# Power_Management.net
KiCad netlist of a schematic drawn in Altium Designer
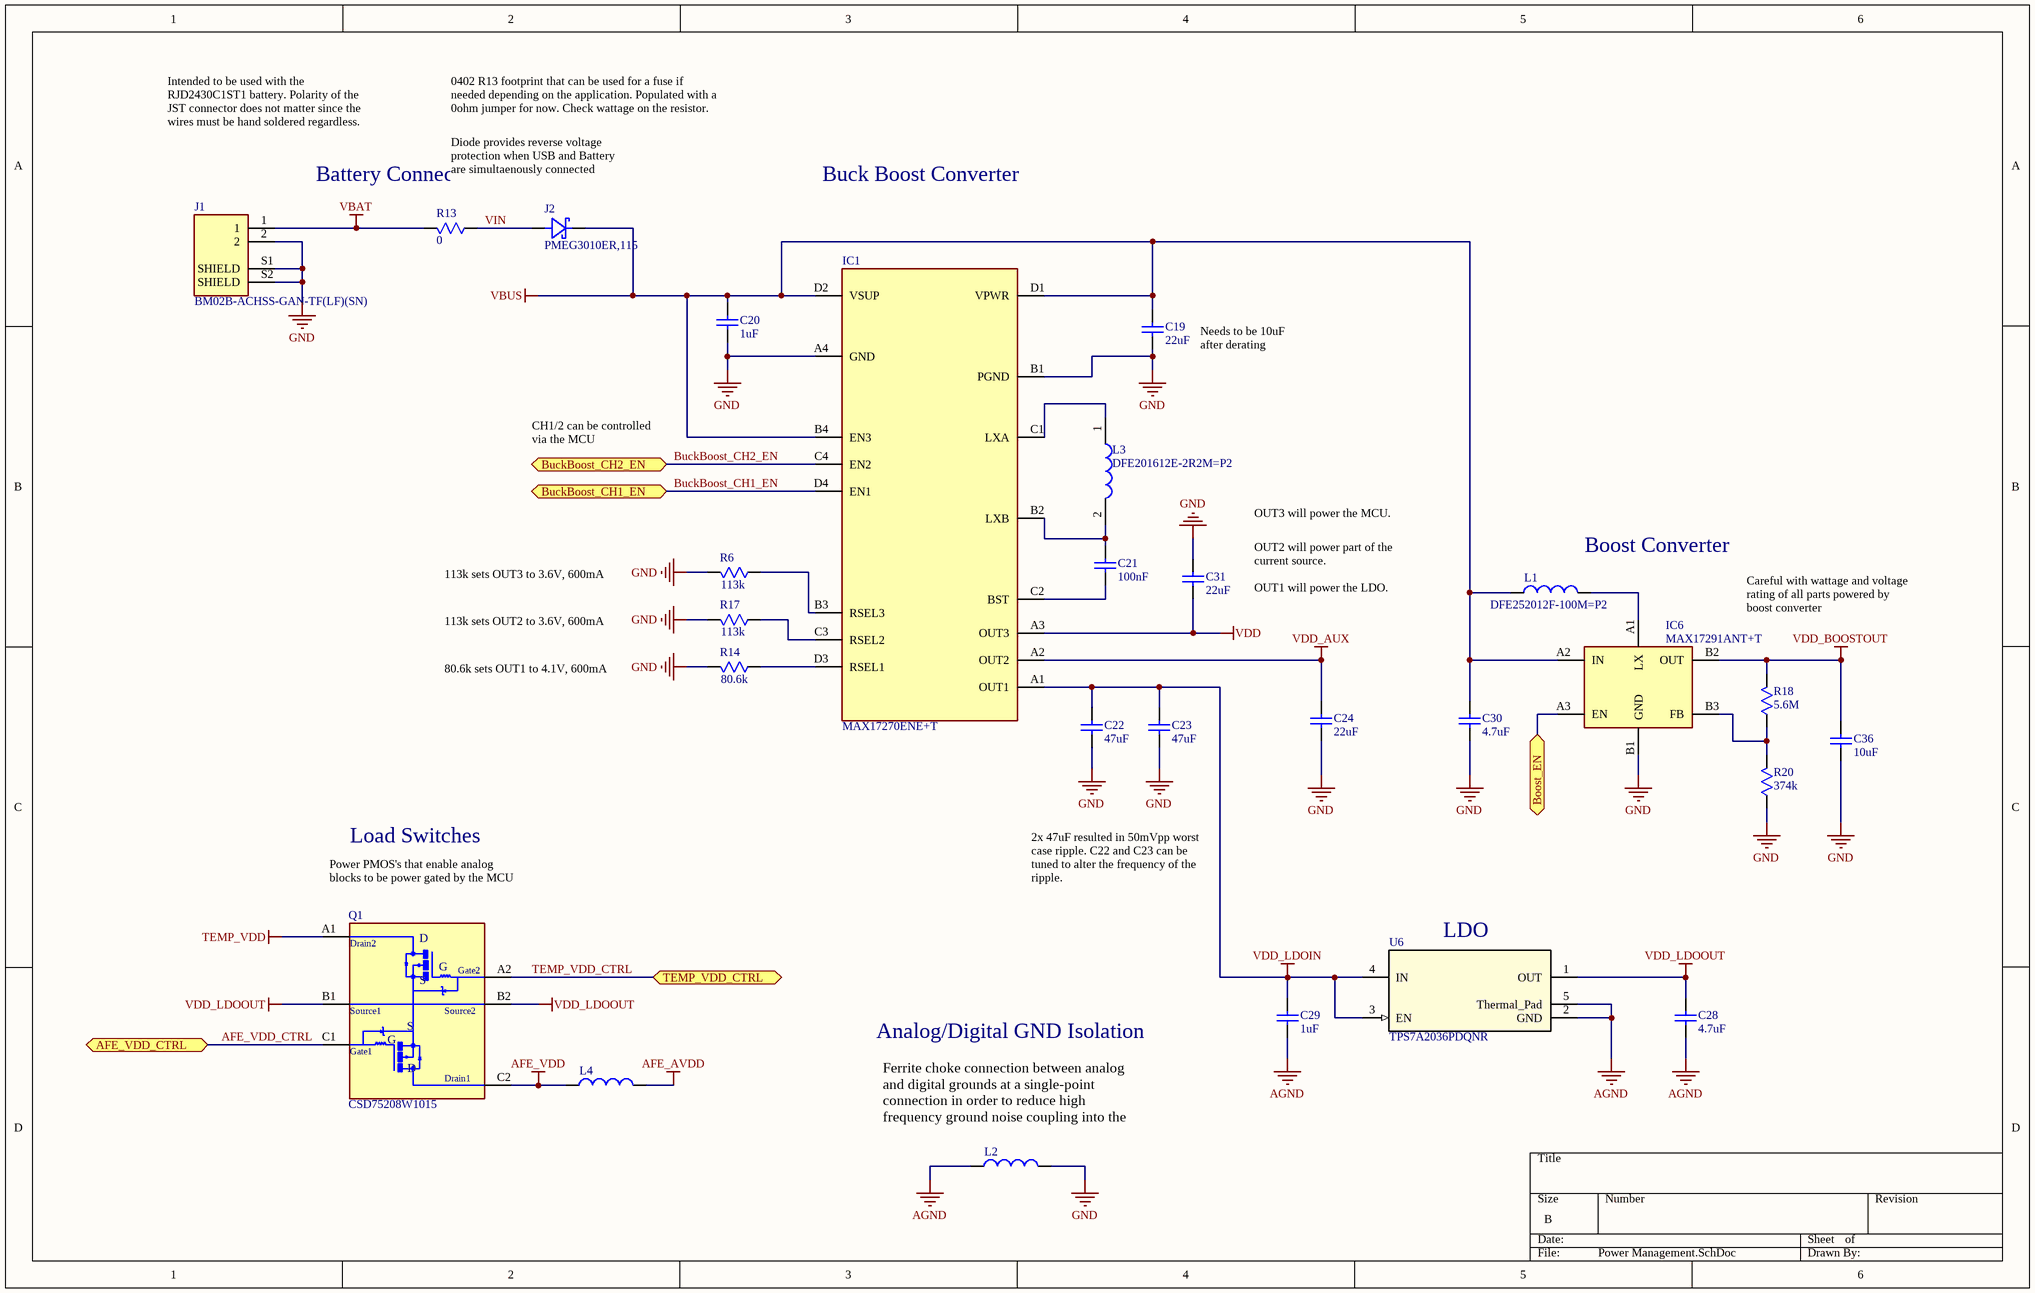
[diagram p0: Power Management.SchDoc]

(export (version "E")
  (design (tool "Eeschema 10.0.6"))
  (components
    (comp (ref "C19")
      (value "22uF")
      (footprint "0402-CAP")
      (description "Multilayer Chip Capacitor")
      (fields (field (name "Comment") "CAP") (field (name "DESIGNER") "OMIGA"))
      (libsource (lib "Schlib") (part "CAP SMD"))
    )
    (comp (ref "C20")
      (value "1uF")
      (footprint "0201 cap")
      (description "Multilayer Chip Capacitor")
      (fields (field (name "Comment") "CAP") (field (name "DESIGNER") "OMIGA"))
      (libsource (lib "Schlib") (part "CAP SMD"))
    )
    (comp (ref "C21")
      (value "100nF")
      (footprint "0201 cap")
      (description "Multilayer Chip Capacitor")
      (fields (field (name "Comment") "CAP") (field (name "DESIGNER") "OMIGA"))
      (libsource (lib "Schlib") (part "CAP SMD"))
    )
    (comp (ref "C22")
      (value "47uF")
      (footprint "0603-CAP")
      (description "Multilayer Chip Capacitor")
      (fields (field (name "Comment") "CAP") (field (name "DESIGNER") "OMIGA"))
      (libsource (lib "Schlib") (part "CAP SMD"))
    )
    (comp (ref "C23")
      (value "47uF")
      (footprint "0603-CAP")
      (description "Multilayer Chip Capacitor")
      (fields (field (name "Comment") "CAP") (field (name "DESIGNER") "OMIGA"))
      (libsource (lib "Schlib") (part "CAP SMD"))
    )
    (comp (ref "C24")
      (value "22uF")
      (footprint "0402-CAP")
      (description "Multilayer Chip Capacitor")
      (fields (field (name "Comment") "CAP") (field (name "DESIGNER") "OMIGA"))
      (libsource (lib "Schlib") (part "CAP SMD"))
    )
    (comp (ref "C28")
      (value "4.7uF")
      (footprint "0201 cap")
      (description "Multilayer Chip Capacitor")
      (fields (field (name "Comment") "CAP") (field (name "DESIGNER") "OMIGA"))
      (libsource (lib "Schlib") (part "CAP SMD"))
    )
    (comp (ref "C29")
      (value "1uF")
      (footprint "0201 cap")
      (description "Multilayer Chip Capacitor")
      (fields (field (name "Comment") "CAP") (field (name "DESIGNER") "OMIGA"))
      (libsource (lib "Schlib") (part "CAP SMD"))
    )
    (comp (ref "C30")
      (value "4.7uF")
      (footprint "0201 cap")
      (description "Multilayer Chip Capacitor")
      (fields (field (name "Comment") "CAP") (field (name "DESIGNER") "OMIGA"))
      (libsource (lib "Schlib") (part "CAP SMD"))
    )
    (comp (ref "C31")
      (value "22uF")
      (footprint "0402-CAP")
      (description "Multilayer Chip Capacitor")
      (fields (field (name "Comment") "CAP") (field (name "DESIGNER") "OMIGA"))
      (libsource (lib "Schlib") (part "CAP SMD"))
    )
    (comp (ref "C36")
      (value "10uF")
      (footprint "0603-CAP")
      (description "Multilayer Chip Capacitor")
      (fields (field (name "Comment") "CAP") (field (name "DESIGNER") "OMIGA"))
      (libsource (lib "Schlib") (part "CAP SMD"))
    )
    (comp (ref "IC1")
      (value "MAX17270ENE+T")
      (footprint "BGA16C40P4X4_177X177X50")
      (description "nanoPower Triple-Output, Single-Inductor,\r\nMultiple-Output (SIMO) Buck-Boost Regulator")
      (libsource (lib "Schlib") (part "MAX17270ENE+T"))
    )
    (comp (ref "IC6")
      (value "MAX17291ANT+T")
      (footprint "Maxim_Integrated_N60N1-1_MFG")
      (description "Integrated Circuit")
      (fields (field (name "MOUSER PART NUMBER") "700-MAX17291ANT+T"))
      (libsource (lib "Schlib") (part "MAX17291ANT+T"))
    )
    (comp (ref "J1")
      (value "BM02B-ACHSS-GAN-TF(LF)(SN)")
      (footprint "JST_BM02B-ACHSS-GAN-TF(LF)(SN)")
      (description "Connector Header Surface Mount, Right Angle 2 position 0.047 (1.20mm)")
      (fields (field (name "MF") "JST Sales"))
      (libsource (lib "Schlib") (part "BM02B-ACHSS-GAN-TF(LF)(SN)"))
    )
    (comp (ref "J2")
      (value "PMEG3010ER,115")
      (footprint "SDO_SOD-123FL_ONS-L")
      (libsource (lib "Schlib") (part "SCHOTTKY_LowVf"))
    )
    (comp (ref "L1")
      (value "DFE252012F-100M=P2")
      (footprint "INDC2520X120N")
      (description "Inductor with Inductance: 10uH Tol. +/-20%, Package: 1008 (2520)")
      (fields (field (name "MF") "Murata Electronics") (field (name "DIGI-KEY_PART_NUMBER") "490-13050-1-ND"))
      (libsource (lib "Schlib") (part "DFE252012F-100M=P2"))
    )
    (comp (ref "L2")
      (value "IND")
      (footprint "0201 ferrite")
      (description "Surface Mount Inductor")
      (fields (field (name "DESIGNER") "OMIGA"))
      (libsource (lib "Schlib") (part "IND SMD"))
    )
    (comp (ref "L3")
      (value "DFE201612E-2R2M=P2")
      (footprint "1286ASH1R0MP2")
      (description "Inductor")
      (fields (field (name "MOUSER2 PART NUMBER") "81-DFE201612E-2R2MP2"))
      (libsource (lib "Schlib") (part "DFE201612E-2R2M=P2"))
    )
    (comp (ref "L4")
      (value "IND")
      (footprint "0201 ferrite")
      (description "Surface Mount Inductor")
      (fields (field (name "DESIGNER") "OMIGA"))
      (libsource (lib "Schlib") (part "IND SMD"))
    )
    (comp (ref "Q1")
      (value "CSD75208W1015")
      (footprint "BGA6C50P2X3_145X95X62")
      (fields (field (name "MF") "Texas Instruments"))
      (libsource (lib "Schlib") (part "CSD75208W1015"))
    )
    (comp (ref "R6")
      (value "113k")
      (footprint "0201 res")
      (description "Surface Mount Resistor")
      (fields (field (name "Comment") "RES") (field (name "DESIGNER") "OMIGA"))
      (libsource (lib "Schlib") (part "RES SMD"))
    )
    (comp (ref "R13")
      (value "0")
      (footprint "0402-RES")
      (description "Surface Mount Resistor")
      (fields (field (name "Comment") "RES") (field (name "DESIGNER") "OMIGA"))
      (libsource (lib "Schlib") (part "RES SMD"))
    )
    (comp (ref "R14")
      (value "80.6k")
      (footprint "0201 res")
      (description "Surface Mount Resistor")
      (fields (field (name "Comment") "RES") (field (name "DESIGNER") "OMIGA"))
      (libsource (lib "Schlib") (part "RES SMD"))
    )
    (comp (ref "R17")
      (value "113k")
      (footprint "0201 res")
      (description "Surface Mount Resistor")
      (fields (field (name "Comment") "RES") (field (name "DESIGNER") "OMIGA"))
      (libsource (lib "Schlib") (part "RES SMD"))
    )
    (comp (ref "R18")
      (value "5.6M")
      (footprint "0201 res")
      (description "Surface Mount Resistor")
      (fields (field (name "Comment") "RES") (field (name "DESIGNER") "OMIGA"))
      (libsource (lib "Schlib") (part "RES SMD"))
    )
    (comp (ref "R20")
      (value "374k")
      (footprint "0201 res")
      (description "Surface Mount Resistor")
      (fields (field (name "Comment") "RES") (field (name "DESIGNER") "OMIGA"))
      (libsource (lib "Schlib") (part "RES SMD"))
    )
    (comp (ref "U6")
      (value "TPS7A2036PDQNR")
      (footprint "DQN0004A-MFG")
      (description "No Description Available")
      (fields (field (name "COPYRIGHT") "Copyright (C) 2022 Ultra Librarian. All rights reserved."))
      (libsource (lib "Schlib") (part "TPS7A2036PDQNR"))
    )
  )
  (nets
    (net (code "1") (name "/AFE_VDD_CTRL") (class "Default")
      (node (ref "Q1") (pin "C1") (pinfunction "GATE1_C1") (pintype "passive"))
    )
    (net (code "2") (name "/Boost_EN") (class "Default")
      (node (ref "IC6") (pin "A3") (pinfunction "EN_A3") (pintype "passive"))
    )
    (net (code "3") (name "/BuckBoost_CH1_EN") (class "Default")
      (node (ref "IC1") (pin "D4") (pinfunction "EN1_D4") (pintype "passive"))
    )
    (net (code "4") (name "/BuckBoost_CH2_EN") (class "Default")
      (node (ref "IC1") (pin "C4") (pinfunction "EN2_C4") (pintype "passive"))
    )
    (net (code "5") (name "/TEMP_VDD_CTRL") (class "Default")
      (node (ref "Q1") (pin "A2") (pinfunction "GATE2_A2") (pintype "passive"))
    )
    (net (code "6") (name "/VIN") (class "Default")
      (node (ref "J2") (pin "2") (pinfunction "12_2") (pintype "passive"))
      (node (ref "R13") (pin "1") (pinfunction "1_1") (pintype "passive"))
    )
    (net (code "7") (name "AFE_AVDD") (class "Default")
      (node (ref "L4") (pin "2") (pinfunction "2_2") (pintype "passive"))
    )
    (net (code "8") (name "AFE_VDD") (class "Default")
      (node (ref "L4") (pin "1") (pinfunction "1_1") (pintype "passive"))
      (node (ref "Q1") (pin "C2") (pinfunction "DRAIN1_C2") (pintype "passive"))
    )
    (net (code "9") (name "AGND") (class "Default")
      (node (ref "C28") (pin "2") (pinfunction "2_2") (pintype "passive"))
      (node (ref "C29") (pin "2") (pinfunction "2_2") (pintype "passive"))
      (node (ref "L2") (pin "1") (pinfunction "1_1") (pintype "passive"))
      (node (ref "U6") (pin "2") (pinfunction "GND_2") (pintype "power_in"))
      (node (ref "U6") (pin "5") (pinfunction "Thermal_Pad_5") (pintype "passive"))
    )
    (net (code "10") (name "GND") (class "Default")
      (node (ref "C19") (pin "2") (pinfunction "2_2") (pintype "passive"))
      (node (ref "C20") (pin "2") (pinfunction "2_2") (pintype "passive"))
      (node (ref "C22") (pin "2") (pinfunction "2_2") (pintype "passive"))
      (node (ref "C23") (pin "2") (pinfunction "2_2") (pintype "passive"))
      (node (ref "C24") (pin "2") (pinfunction "2_2") (pintype "passive"))
      (node (ref "C30") (pin "2") (pinfunction "2_2") (pintype "passive"))
      (node (ref "C31") (pin "2") (pinfunction "2_2") (pintype "passive"))
      (node (ref "C36") (pin "2") (pinfunction "2_2") (pintype "passive"))
      (node (ref "IC1") (pin "A4") (pinfunction "GND_A4") (pintype "passive"))
      (node (ref "IC1") (pin "B1") (pinfunction "PGND_B1") (pintype "passive"))
      (node (ref "IC6") (pin "B1") (pinfunction "GND_B1") (pintype "passive"))
      (node (ref "J1") (pin "2") (pinfunction "2_2") (pintype "passive"))
      (node (ref "J1") (pin "S1") (pinfunction "SHIELD_S1") (pintype "passive"))
      (node (ref "J1") (pin "S2") (pinfunction "SHIELD_S2") (pintype "passive"))
      (node (ref "L2") (pin "2") (pinfunction "2_2") (pintype "passive"))
      (node (ref "R14") (pin "2") (pinfunction "2_2") (pintype "passive"))
      (node (ref "R17") (pin "2") (pinfunction "2_2") (pintype "passive"))
      (node (ref "R20") (pin "1") (pinfunction "1_1") (pintype "passive"))
      (node (ref "R6") (pin "2") (pinfunction "2_2") (pintype "passive"))
    )
    (net (code "11") (name "Net-(IC1-BST)") (class "Default")
      (node (ref "C21") (pin "2") (pinfunction "2_2") (pintype "passive"))
      (node (ref "IC1") (pin "C2") (pinfunction "BST_C2") (pintype "passive"))
    )
    (net (code "12") (name "Net-(IC1-LXA)") (class "Default")
      (node (ref "IC1") (pin "C1") (pinfunction "LXA_C1") (pintype "passive"))
      (node (ref "L3") (pin "1") (pinfunction "1_1") (pintype "passive"))
    )
    (net (code "13") (name "Net-(IC1-LXB)") (class "Default")
      (node (ref "C21") (pin "1") (pinfunction "1_1") (pintype "passive"))
      (node (ref "IC1") (pin "B2") (pinfunction "LXB_B2") (pintype "passive"))
      (node (ref "L3") (pin "2") (pinfunction "2_2") (pintype "passive"))
    )
    (net (code "14") (name "Net-(IC1-RSEL1)") (class "Default")
      (node (ref "IC1") (pin "D3") (pinfunction "RSEL1_D3") (pintype "passive"))
      (node (ref "R14") (pin "1") (pinfunction "1_1") (pintype "passive"))
    )
    (net (code "15") (name "Net-(IC1-RSEL2)") (class "Default")
      (node (ref "IC1") (pin "C3") (pinfunction "RSEL2_C3") (pintype "passive"))
      (node (ref "R17") (pin "1") (pinfunction "1_1") (pintype "passive"))
    )
    (net (code "16") (name "Net-(IC1-RSEL3)") (class "Default")
      (node (ref "IC1") (pin "B3") (pinfunction "RSEL3_B3") (pintype "passive"))
      (node (ref "R6") (pin "1") (pinfunction "1_1") (pintype "passive"))
    )
    (net (code "17") (name "Net-(IC6-FB)") (class "Default")
      (node (ref "IC6") (pin "B3") (pinfunction "FB_B3") (pintype "passive"))
      (node (ref "R18") (pin "1") (pinfunction "1_1") (pintype "passive"))
      (node (ref "R20") (pin "2") (pinfunction "2_2") (pintype "passive"))
    )
    (net (code "18") (name "Net-(IC6-LX)") (class "Default")
      (node (ref "IC6") (pin "A1") (pinfunction "LX_A1") (pintype "passive"))
      (node (ref "L1") (pin "2") (pinfunction "2_2") (pintype "passive"))
    )
    (net (code "19") (name "TEMP_VDD") (class "Default")
      (node (ref "Q1") (pin "A1") (pinfunction "DRAIN2_A1") (pintype "passive"))
    )
    (net (code "20") (name "VBAT") (class "Default")
      (node (ref "J1") (pin "1") (pinfunction "1_1") (pintype "passive"))
      (node (ref "R13") (pin "2") (pinfunction "2_2") (pintype "passive"))
    )
    (net (code "21") (name "VBUS") (class "Default")
      (node (ref "C19") (pin "1") (pinfunction "1_1") (pintype "passive"))
      (node (ref "C20") (pin "1") (pinfunction "1_1") (pintype "passive"))
      (node (ref "C30") (pin "1") (pinfunction "1_1") (pintype "passive"))
      (node (ref "IC1") (pin "B4") (pinfunction "EN3_B4") (pintype "passive"))
      (node (ref "IC1") (pin "D1") (pinfunction "VPWR_D1") (pintype "passive"))
      (node (ref "IC1") (pin "D2") (pinfunction "VSUP_D2") (pintype "passive"))
      (node (ref "IC6") (pin "A2") (pinfunction "IN_A2") (pintype "passive"))
      (node (ref "J2") (pin "1") (pinfunction "11_1") (pintype "passive"))
      (node (ref "L1") (pin "1") (pinfunction "1_1") (pintype "passive"))
    )
    (net (code "22") (name "VDD") (class "Default")
      (node (ref "C31") (pin "1") (pinfunction "1_1") (pintype "passive"))
      (node (ref "IC1") (pin "A3") (pinfunction "OUT3_A3") (pintype "passive"))
    )
    (net (code "23") (name "VDD_AUX") (class "Default")
      (node (ref "C24") (pin "1") (pinfunction "1_1") (pintype "passive"))
      (node (ref "IC1") (pin "A2") (pinfunction "OUT2_A2") (pintype "passive"))
    )
    (net (code "24") (name "VDD_BOOSTOUT") (class "Default")
      (node (ref "C36") (pin "1") (pinfunction "1_1") (pintype "passive"))
      (node (ref "IC6") (pin "B2") (pinfunction "OUT_B2") (pintype "passive"))
      (node (ref "R18") (pin "2") (pinfunction "2_2") (pintype "passive"))
    )
    (net (code "25") (name "VDD_LDOIN") (class "Default")
      (node (ref "C22") (pin "1") (pinfunction "1_1") (pintype "passive"))
      (node (ref "C23") (pin "1") (pinfunction "1_1") (pintype "passive"))
      (node (ref "C29") (pin "1") (pinfunction "1_1") (pintype "passive"))
      (node (ref "IC1") (pin "A1") (pinfunction "OUT1_A1") (pintype "passive"))
      (node (ref "U6") (pin "3") (pinfunction "EN_3") (pintype "input"))
      (node (ref "U6") (pin "4") (pinfunction "IN_4") (pintype "power_in"))
    )
    (net (code "26") (name "VDD_LDOOUT") (class "Default")
      (node (ref "C28") (pin "1") (pinfunction "1_1") (pintype "passive"))
      (node (ref "Q1") (pin "B1") (pinfunction "SOURCE1_B1") (pintype "passive"))
      (node (ref "Q1") (pin "B2") (pinfunction "SOURCE2_B2") (pintype "passive"))
      (node (ref "U6") (pin "1") (pinfunction "OUT_1") (pintype "passive"))
    )
  )
)
